# 2.net
KiCad netlist of a schematic drawn in Altium Designer
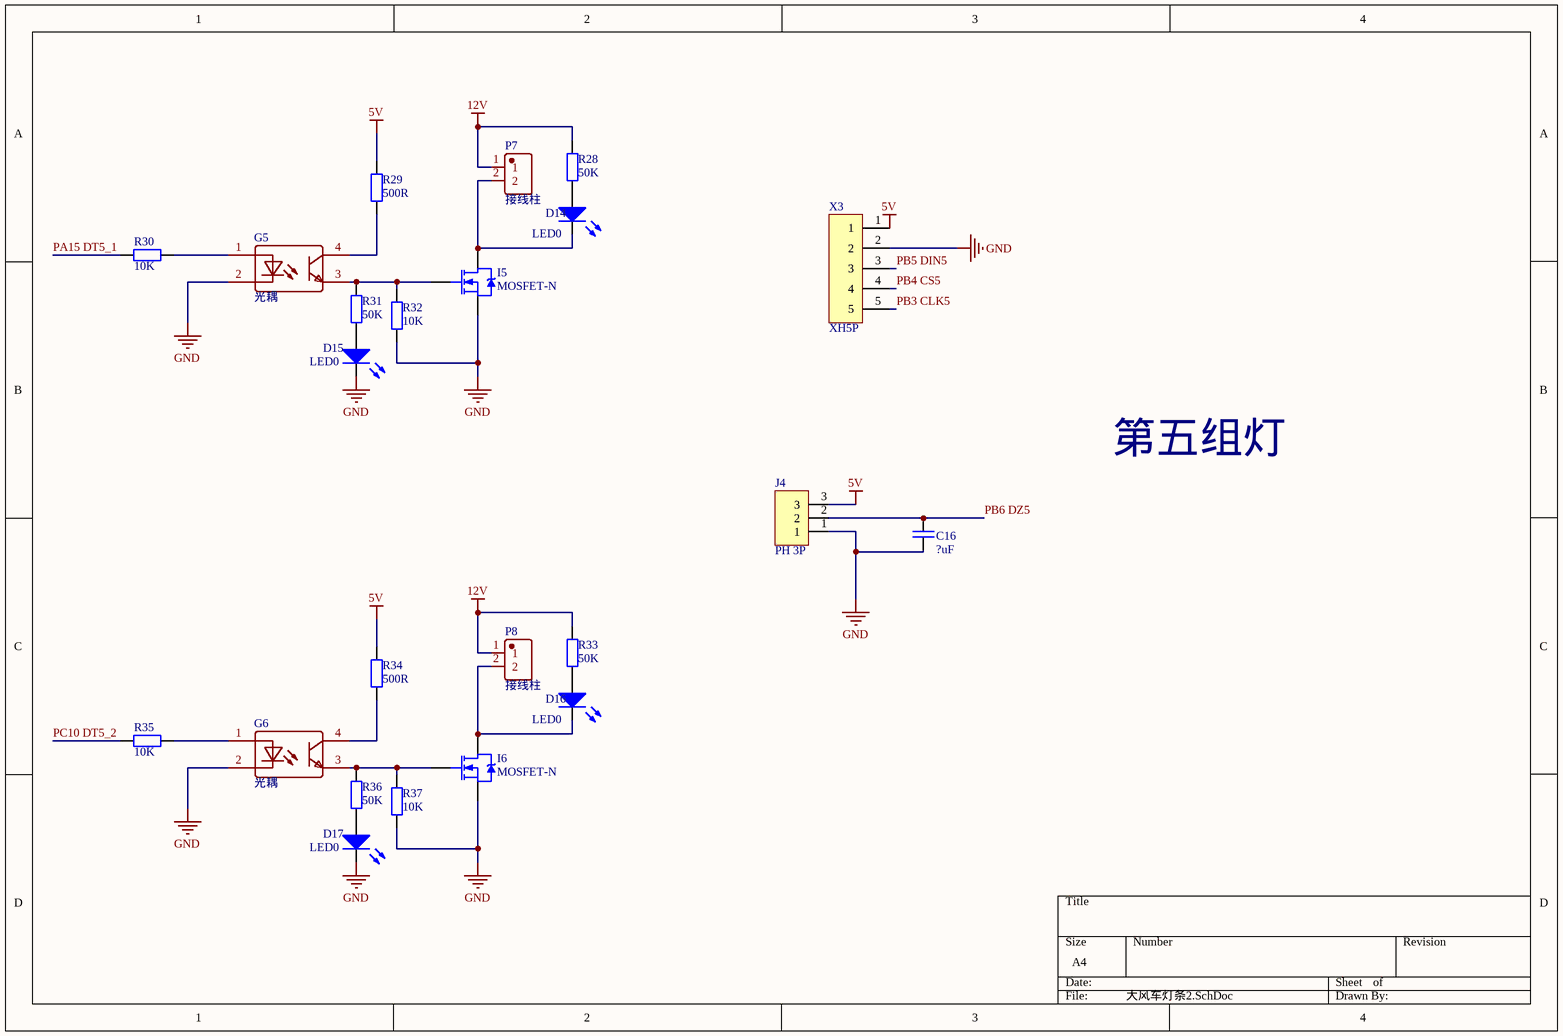
[diagram p0: 大风车灯条2.SchDoc]

(export (version "E")
  (design (tool "Eeschema 10.0.6"))
  (components
    (comp (ref "C16")
      (value "?uF")
      (footprint "0603_C")
      (fields (field (name "PUBLISHER") "Altium Limited"))
      (libsource (lib "电容-电阻-电感") (part "Cap"))
    )
    (comp (ref "D14")
      (value "LED0")
      (footprint "LED-0603")
      (description "发光二极管")
      (fields (field (name "PUBLISHER") "Altium Limited"))
      (libsource (lib "二极管-晶体管") (part "LED0"))
    )
    (comp (ref "D15")
      (value "LED0")
      (footprint "LED-0603")
      (description "发光二极管")
      (fields (field (name "PUBLISHER") "Altium Limited"))
      (libsource (lib "二极管-晶体管") (part "LED0"))
    )
    (comp (ref "D16")
      (value "LED0")
      (footprint "LED-0603")
      (description "发光二极管")
      (fields (field (name "PUBLISHER") "Altium Limited"))
      (libsource (lib "二极管-晶体管") (part "LED0"))
    )
    (comp (ref "D17")
      (value "LED0")
      (footprint "LED-0603")
      (description "发光二极管")
      (fields (field (name "PUBLISHER") "Altium Limited"))
      (libsource (lib "二极管-晶体管") (part "LED0"))
    )
    (comp (ref "G5") (value "光耦") (footprint "SMD-4") (libsource (lib "大风车") (part "光耦")))
    (comp (ref "G6") (value "光耦") (footprint "SMD-4") (libsource (lib "大风车") (part "光耦")))
    (comp (ref "I5") (value "MOSFET-N") (footprint "VSONP-8") (libsource (lib "大风兄弟") (part "MOSFET-N")))
    (comp (ref "I6") (value "MOSFET-N") (footprint "VSONP-8") (libsource (lib "大风兄弟") (part "MOSFET-N")))
    (comp (ref "J4") (value "PH 3P") (footprint "PH3P") (libsource (lib "连接器") (part "PH 3P")))
    (comp (ref "P7") (value "接线柱") (footprint "XT30-F") (libsource (lib "大风车") (part "接线柱")))
    (comp (ref "P8") (value "接线柱") (footprint "XT30-F") (libsource (lib "大风车") (part "接线柱")))
    (comp (ref "R28")
      (value "50K")
      (footprint "0603_R")
      (fields (field (name "PUBLISHER") "Altium Limited"))
      (libsource (lib "") (part "Res_1"))
    )
    (comp (ref "R29")
      (value "500R")
      (footprint "0603_R")
      (fields (field (name "PUBLISHER") "Altium Limited"))
      (libsource (lib "") (part "Res_1"))
    )
    (comp (ref "R30")
      (value "10K")
      (footprint "0603_R")
      (fields (field (name "PUBLISHER") "Altium Limited"))
      (libsource (lib "电容-电阻-电感") (part "Res"))
    )
    (comp (ref "R31")
      (value "50K")
      (footprint "0603_R")
      (fields (field (name "PUBLISHER") "Altium Limited"))
      (libsource (lib "") (part "Res_1"))
    )
    (comp (ref "R32")
      (value "10K")
      (footprint "0603_R")
      (fields (field (name "PUBLISHER") "Altium Limited"))
      (libsource (lib "") (part "Res_1"))
    )
    (comp (ref "R33")
      (value "50K")
      (footprint "0603_R")
      (fields (field (name "PUBLISHER") "Altium Limited"))
      (libsource (lib "") (part "Res_1"))
    )
    (comp (ref "R34")
      (value "500R")
      (footprint "0603_R")
      (fields (field (name "PUBLISHER") "Altium Limited"))
      (libsource (lib "") (part "Res_1"))
    )
    (comp (ref "R35")
      (value "10K")
      (footprint "0603_R")
      (fields (field (name "PUBLISHER") "Altium Limited"))
      (libsource (lib "电容-电阻-电感") (part "Res"))
    )
    (comp (ref "R36")
      (value "50K")
      (footprint "0603_R")
      (fields (field (name "PUBLISHER") "Altium Limited"))
      (libsource (lib "") (part "Res_1"))
    )
    (comp (ref "R37")
      (value "10K")
      (footprint "0603_R")
      (fields (field (name "PUBLISHER") "Altium Limited"))
      (libsource (lib "") (part "Res_1"))
    )
    (comp (ref "X3") (value "XH5P") (footprint "XH5P") (libsource (lib "大风车") (part "XH5P")))
  )
  (nets
    (net (code "1") (name "/PA15 DT5_1") (class "Default")
      (node (ref "R30") (pin "1") (pinfunction "1_1") (pintype "passive"))
    )
    (net (code "2") (name "/PB3 CLK5") (class "Default")
      (node (ref "X3") (pin "5") (pinfunction "5_5") (pintype "power_in"))
    )
    (net (code "3") (name "/PB4 CS5") (class "Default")
      (node (ref "X3") (pin "4") (pinfunction "4_4") (pintype "passive"))
    )
    (net (code "4") (name "/PB5 DIN5") (class "Default")
      (node (ref "X3") (pin "3") (pinfunction "3_3") (pintype "passive"))
    )
    (net (code "5") (name "/PB6 DZ5") (class "Default")
      (node (ref "C16") (pin "2") (pinfunction "2_2") (pintype "passive"))
      (node (ref "J4") (pin "2") (pinfunction "2_2") (pintype "power_in"))
    )
    (net (code "6") (name "/PC10 DT5_2") (class "Default")
      (node (ref "R35") (pin "1") (pinfunction "1_1") (pintype "passive"))
    )
    (net (code "7") (name "5V") (class "Default")
      (node (ref "J4") (pin "3") (pinfunction "3_3") (pintype "power_in"))
      (node (ref "R29") (pin "2") (pinfunction "2_2") (pintype "passive"))
      (node (ref "R34") (pin "2") (pinfunction "2_2") (pintype "passive"))
      (node (ref "X3") (pin "1") (pinfunction "1_1") (pintype "passive"))
    )
    (net (code "8") (name "12V") (class "Default")
      (node (ref "P7") (pin "1") (pinfunction "1_1") (pintype "passive"))
      (node (ref "P8") (pin "1") (pinfunction "1_1") (pintype "passive"))
      (node (ref "R28") (pin "2") (pinfunction "2_2") (pintype "passive"))
      (node (ref "R33") (pin "2") (pinfunction "2_2") (pintype "passive"))
    )
    (net (code "9") (name "GND") (class "Default")
      (node (ref "C16") (pin "1") (pinfunction "1_1") (pintype "passive"))
      (node (ref "D15") (pin "2") (pinfunction "K_2") (pintype "passive"))
      (node (ref "D17") (pin "2") (pinfunction "K_2") (pintype "passive"))
      (node (ref "G5") (pin "2") (pinfunction "CAT_2") (pintype "passive"))
      (node (ref "G6") (pin "2") (pinfunction "CAT_2") (pintype "passive"))
      (node (ref "I5") (pin "S") (pinfunction "S_S") (pintype "passive"))
      (node (ref "I6") (pin "S") (pinfunction "S_S") (pintype "passive"))
      (node (ref "J4") (pin "1") (pinfunction "1_1") (pintype "power_in"))
      (node (ref "R32") (pin "1") (pinfunction "1_1") (pintype "passive"))
      (node (ref "R37") (pin "1") (pinfunction "1_1") (pintype "passive"))
      (node (ref "X3") (pin "2") (pinfunction "2_2") (pintype "passive"))
    )
    (net (code "10") (name "Net-(D14-A)") (class "Default")
      (node (ref "D14") (pin "1") (pinfunction "A_1") (pintype "passive"))
      (node (ref "R28") (pin "1") (pinfunction "1_1") (pintype "passive"))
    )
    (net (code "11") (name "Net-(D14-K)") (class "Default")
      (node (ref "D14") (pin "2") (pinfunction "K_2") (pintype "passive"))
      (node (ref "I5") (pin "D") (pinfunction "D_D") (pintype "passive"))
      (node (ref "P7") (pin "2") (pinfunction "2_2") (pintype "passive"))
    )
    (net (code "12") (name "Net-(D15-A)") (class "Default")
      (node (ref "D15") (pin "1") (pinfunction "A_1") (pintype "passive"))
      (node (ref "R31") (pin "1") (pinfunction "1_1") (pintype "passive"))
    )
    (net (code "13") (name "Net-(D16-A)") (class "Default")
      (node (ref "D16") (pin "1") (pinfunction "A_1") (pintype "passive"))
      (node (ref "R33") (pin "1") (pinfunction "1_1") (pintype "passive"))
    )
    (net (code "14") (name "Net-(D16-K)") (class "Default")
      (node (ref "D16") (pin "2") (pinfunction "K_2") (pintype "passive"))
      (node (ref "I6") (pin "D") (pinfunction "D_D") (pintype "passive"))
      (node (ref "P8") (pin "2") (pinfunction "2_2") (pintype "passive"))
    )
    (net (code "15") (name "Net-(D17-A)") (class "Default")
      (node (ref "D17") (pin "1") (pinfunction "A_1") (pintype "passive"))
      (node (ref "R36") (pin "1") (pinfunction "1_1") (pintype "passive"))
    )
    (net (code "16") (name "Net-(G5-AN)") (class "Default")
      (node (ref "G5") (pin "1") (pinfunction "AN_1") (pintype "passive"))
      (node (ref "R30") (pin "2") (pinfunction "2_2") (pintype "passive"))
    )
    (net (code "17") (name "Net-(G5-COL)") (class "Default")
      (node (ref "G5") (pin "4") (pinfunction "COL_4") (pintype "passive"))
      (node (ref "R29") (pin "1") (pinfunction "1_1") (pintype "passive"))
    )
    (net (code "18") (name "Net-(G5-EM)") (class "Default")
      (node (ref "G5") (pin "3") (pinfunction "EM_3") (pintype "passive"))
      (node (ref "I5") (pin "G") (pinfunction "G_G") (pintype "passive"))
      (node (ref "R31") (pin "2") (pinfunction "2_2") (pintype "passive"))
      (node (ref "R32") (pin "2") (pinfunction "2_2") (pintype "passive"))
    )
    (net (code "19") (name "Net-(G6-AN)") (class "Default")
      (node (ref "G6") (pin "1") (pinfunction "AN_1") (pintype "passive"))
      (node (ref "R35") (pin "2") (pinfunction "2_2") (pintype "passive"))
    )
    (net (code "20") (name "Net-(G6-COL)") (class "Default")
      (node (ref "G6") (pin "4") (pinfunction "COL_4") (pintype "passive"))
      (node (ref "R34") (pin "1") (pinfunction "1_1") (pintype "passive"))
    )
    (net (code "21") (name "Net-(G6-EM)") (class "Default")
      (node (ref "G6") (pin "3") (pinfunction "EM_3") (pintype "passive"))
      (node (ref "I6") (pin "G") (pinfunction "G_G") (pintype "passive"))
      (node (ref "R36") (pin "2") (pinfunction "2_2") (pintype "passive"))
      (node (ref "R37") (pin "2") (pinfunction "2_2") (pintype "passive"))
    )
  )
)
